# AC_fan.net
KiCad netlist of a schematic drawn in Altium Designer
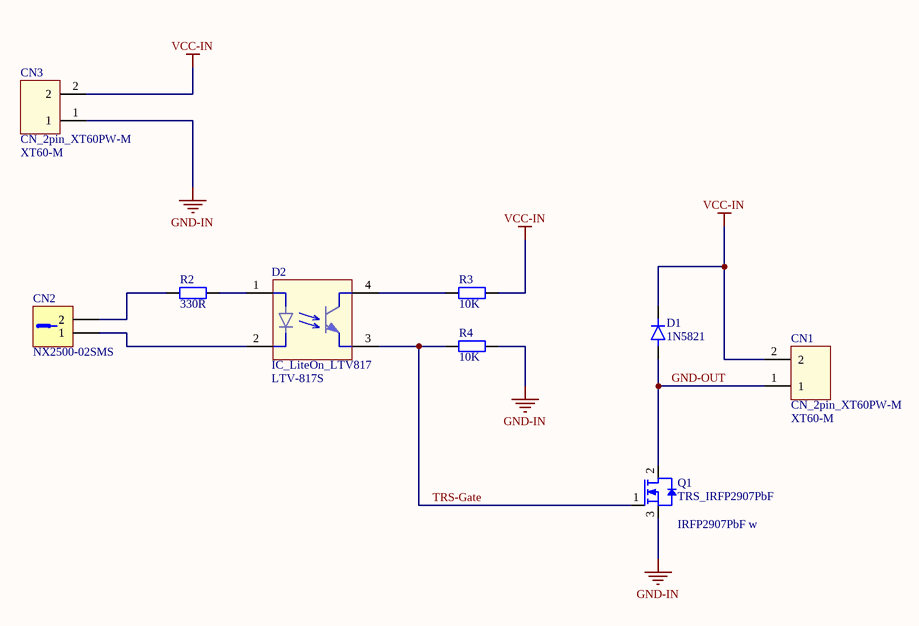
[diagram p0: AC_fan.SchDoc]

(export (version "E")
  (design (tool "Eeschema 10.0.6"))
  (components
    (comp (ref "CN1")
      (value "CN_2pin_XT60PW-M")
      (footprint "CN_2pin_XT60-M")
      (description "30A, 2 pin")
      (fields (field (name "VALUE1") "XT60-M") (field (name "MANUFACTURER") "AMASS"))
      (libsource (lib "") (part "CN_2pin_XT60PW-M_1"))
    )
    (comp (ref "CN2")
      (value "CN_1X2M")
      (footprint "CN_XH2.54-2P-MALE")
      (fields (field (name "VALUE1") "NX2500-02SMS") (field (name "MANUFACTURER") "Joint Tech"))
      (libsource (lib "DSW_Lib") (part "CN_1X2M"))
    )
    (comp (ref "CN3")
      (value "CN_2pin_XT60PW-M")
      (footprint "CN_2pin_XT60-M")
      (description "30A, 2 pin")
      (fields (field (name "VALUE1") "XT60-M") (field (name "MANUFACTURER") "AMASS"))
      (libsource (lib "DSW_Lib") (part "CN_2pin_XT60PW-M"))
    )
    (comp (ref "D1")
      (value "DIO")
      (footprint "DO-201AD-Horizontal")
      (description "Schottky Diodes & Rectifiers 3 Amp 30 Volt")
      (fields (field (name "VALUE1") "1N5821") (field (name "MANUFACTURER") "Diodes"))
      (libsource (lib "DSW_Lib") (part "DIO"))
    )
    (comp (ref "D2")
      (value "IC_LiteOn_LTV817")
      (footprint "IC_LiteOn_ LTV-817S")
      (description "Transistor Output Optocouplers Optocoupler Phototrans")
      (fields (field (name "VALUE1") "LTV-817S") (field (name "MANUFACTURER") "Lite-On"))
      (libsource (lib "DSW_Lib") (part "IC_LiteOn_LTV817"))
    )
    (comp (ref "Q1")
      (value "TRS_IRFP2907PbF")
      (footprint "TO-247AC")
      (description "N-channel Power MOSFET Si 75V 209A 3-Pin(3+Tab)")
      (fields
        (field (name "VALUE1") "IRFP2907PbF\r\nw")
        (field (name "MANUFACTURER") "International Rectifier")
      )
      (libsource (lib "DSW_Lib") (part "TRS_IRFP2907PbF"))
    )
    (comp (ref "R2")
      (value "RES")
      (footprint "RESC2012X60N")
      (description "RESISTOR, 0805, 330R, 1%, SMD")
      (fields (field (name "VALUE1") "330R") (field (name "MANUFACTURER") "Yageo"))
      (libsource (lib "DSW_Lib") (part "RES"))
    )
    (comp (ref "R3")
      (value "RES")
      (footprint "RESC2012X60N")
      (description "RESISTOR, 0805, 10K, 1%, SMD")
      (fields (field (name "VALUE1") "10K") (field (name "MANUFACTURER") "Yageo"))
      (libsource (lib "DSW_Lib") (part "RES"))
    )
    (comp (ref "R4")
      (value "RES")
      (footprint "RESC2012X60N")
      (description "RESISTOR, 0805, 10K, 1%, SMD")
      (fields (field (name "VALUE1") "10K") (field (name "MANUFACTURER") "Yageo"))
      (libsource (lib "DSW_Lib") (part "RES"))
    )
  )
  (nets
    (net (code "1") (name "/GND-OUT") (class "Default")
      (node (ref "CN1") (pin "1") (pinfunction "1_1") (pintype "passive"))
      (node (ref "D1") (pin "2") (pinfunction "A_2") (pintype "passive"))
      (node (ref "Q1") (pin "2") (pinfunction "D_2") (pintype "passive"))
    )
    (net (code "2") (name "/TRS-Gate") (class "Default")
      (node (ref "D2") (pin "3") (pinfunction "3_3") (pintype "passive"))
      (node (ref "Q1") (pin "1") (pinfunction "G_1") (pintype "passive"))
      (node (ref "R4") (pin "1") (pinfunction "1_1") (pintype "passive"))
    )
    (net (code "3") (name "GND-IN") (class "Default")
      (node (ref "CN3") (pin "1") (pinfunction "1_1") (pintype "passive"))
      (node (ref "Q1") (pin "3") (pinfunction "S_3") (pintype "passive"))
      (node (ref "R4") (pin "2") (pinfunction "2_2") (pintype "passive"))
    )
    (net (code "4") (name "Net-(CN2-Pad1)") (class "Default")
      (node (ref "CN2") (pin "1") (pinfunction "1_1") (pintype "passive"))
      (node (ref "D2") (pin "2") (pinfunction "2_2") (pintype "passive"))
    )
    (net (code "5") (name "Net-(CN2-Pad2)") (class "Default")
      (node (ref "CN2") (pin "2") (pinfunction "2_2") (pintype "passive"))
      (node (ref "R2") (pin "1") (pinfunction "1_1") (pintype "passive"))
    )
    (net (code "6") (name "Net-(D2-Pad1)") (class "Default")
      (node (ref "D2") (pin "1") (pinfunction "1_1") (pintype "passive"))
      (node (ref "R2") (pin "2") (pinfunction "2_2") (pintype "passive"))
    )
    (net (code "7") (name "Net-(D2-Pad4)") (class "Default")
      (node (ref "D2") (pin "4") (pinfunction "4_4") (pintype "passive"))
      (node (ref "R3") (pin "1") (pinfunction "1_1") (pintype "passive"))
    )
    (net (code "8") (name "VCC-IN") (class "Default")
      (node (ref "CN1") (pin "2") (pinfunction "2_2") (pintype "passive"))
      (node (ref "CN3") (pin "2") (pinfunction "2_2") (pintype "passive"))
      (node (ref "D1") (pin "1") (pinfunction "K_1") (pintype "passive"))
      (node (ref "R3") (pin "2") (pinfunction "2_2") (pintype "passive"))
    )
  )
)
